# MEGA2560_Rev3e.net
KiCad netlist of a schematic drawn in EAGLE
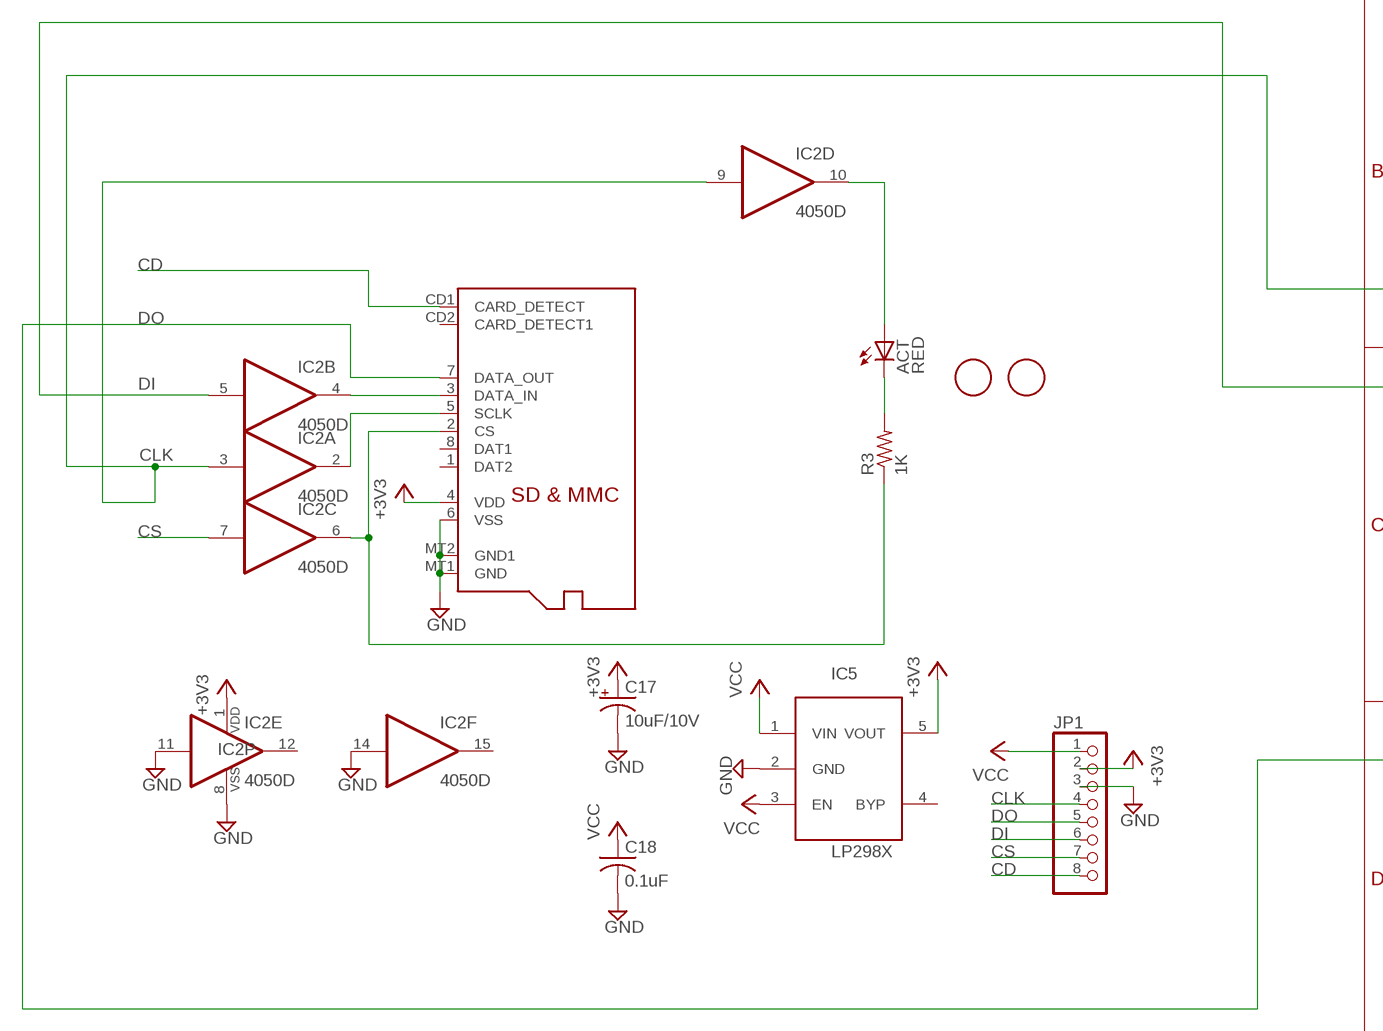
[diagram p0: schematic, sheet 1, part 1 of 2]
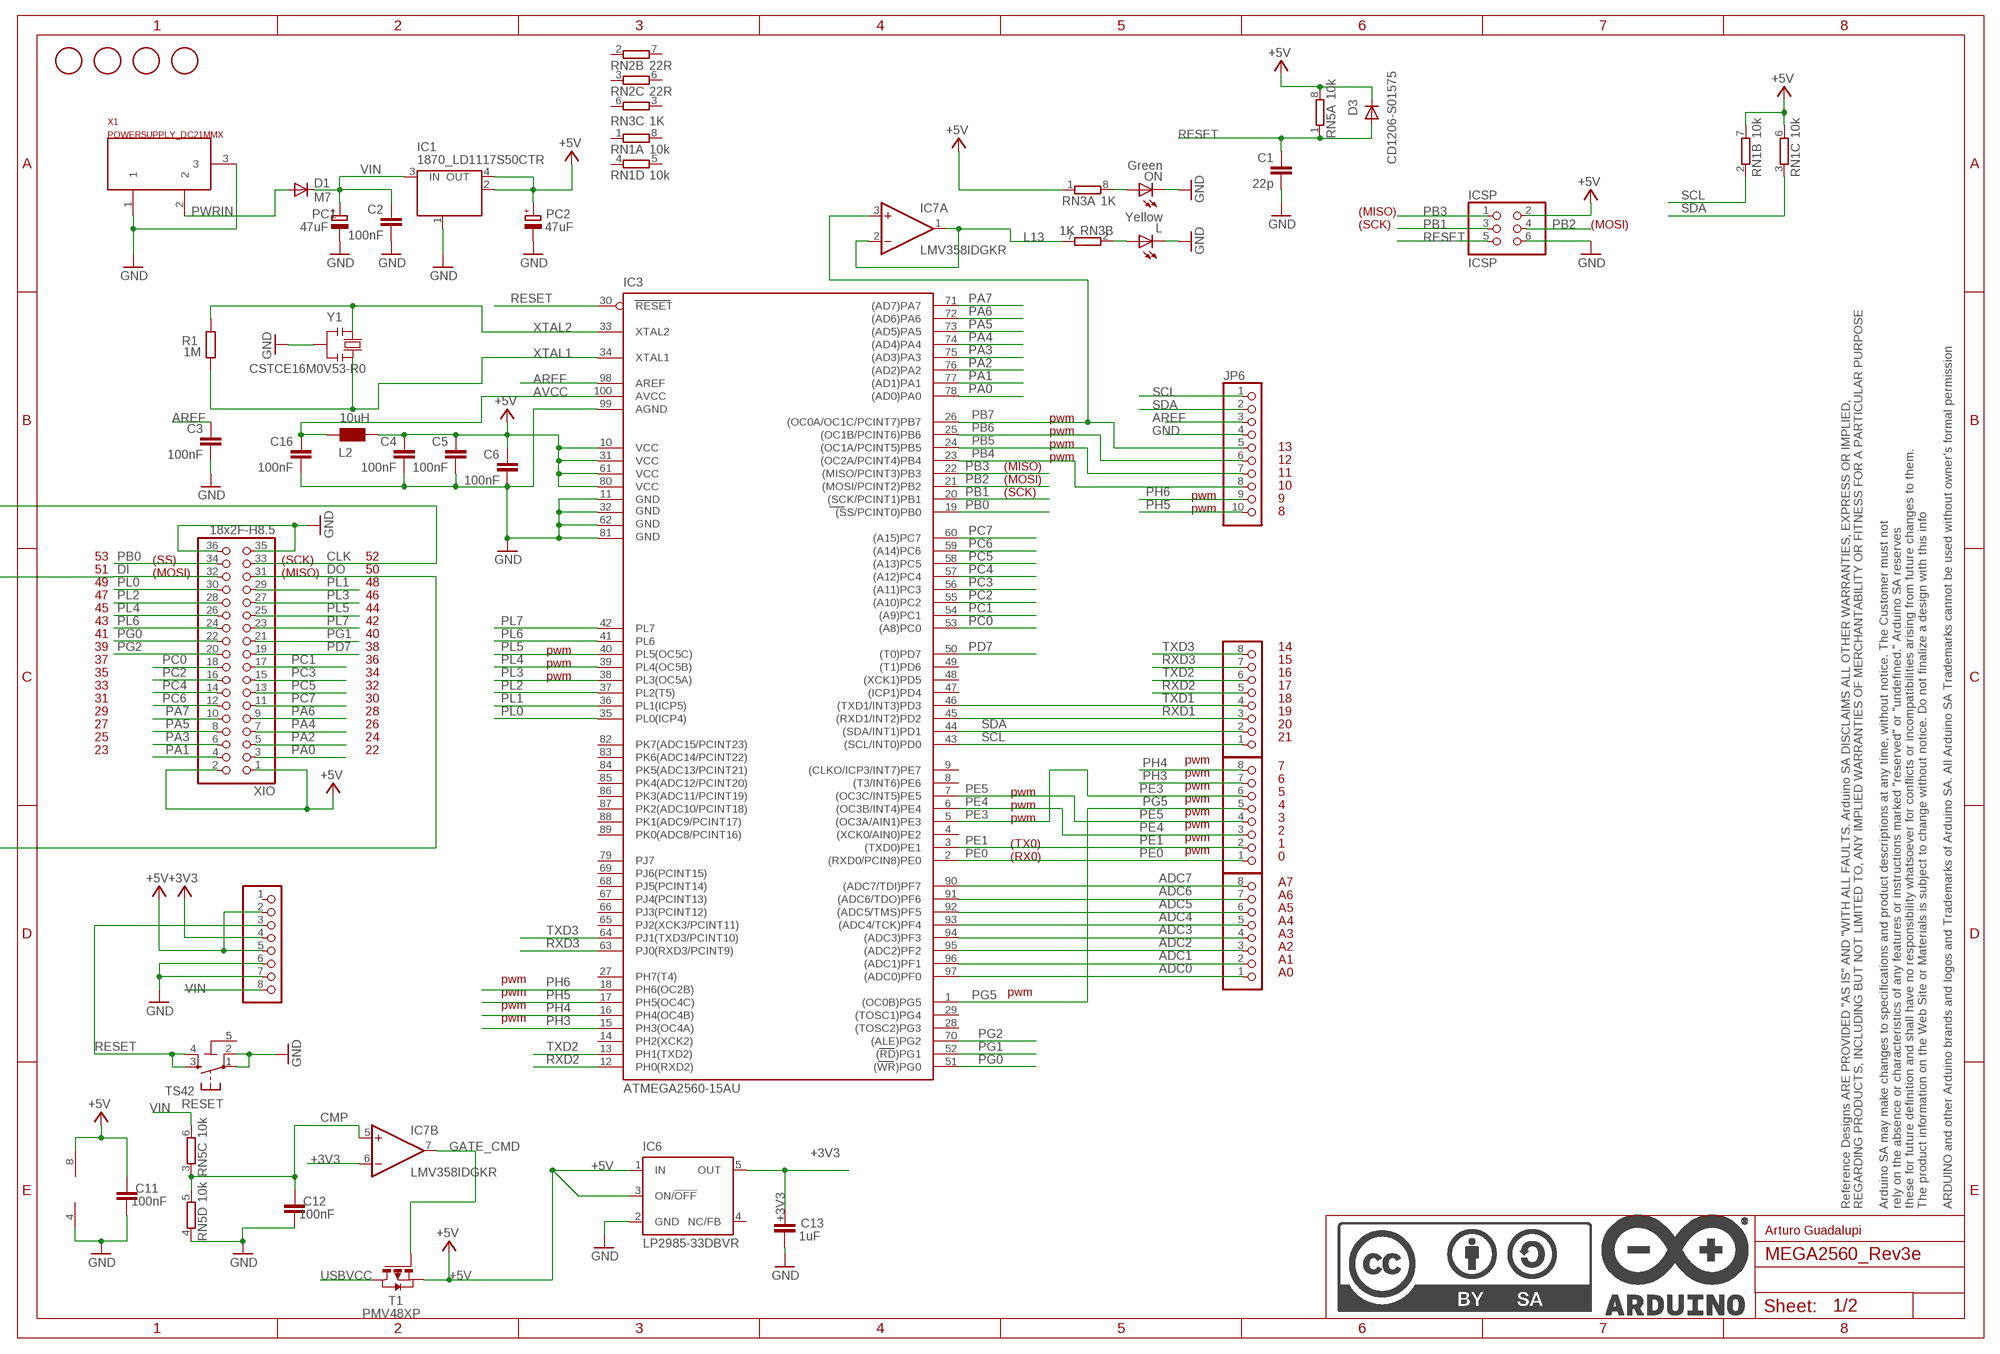
[diagram p1: schematic, sheet 1, part 2 of 2]
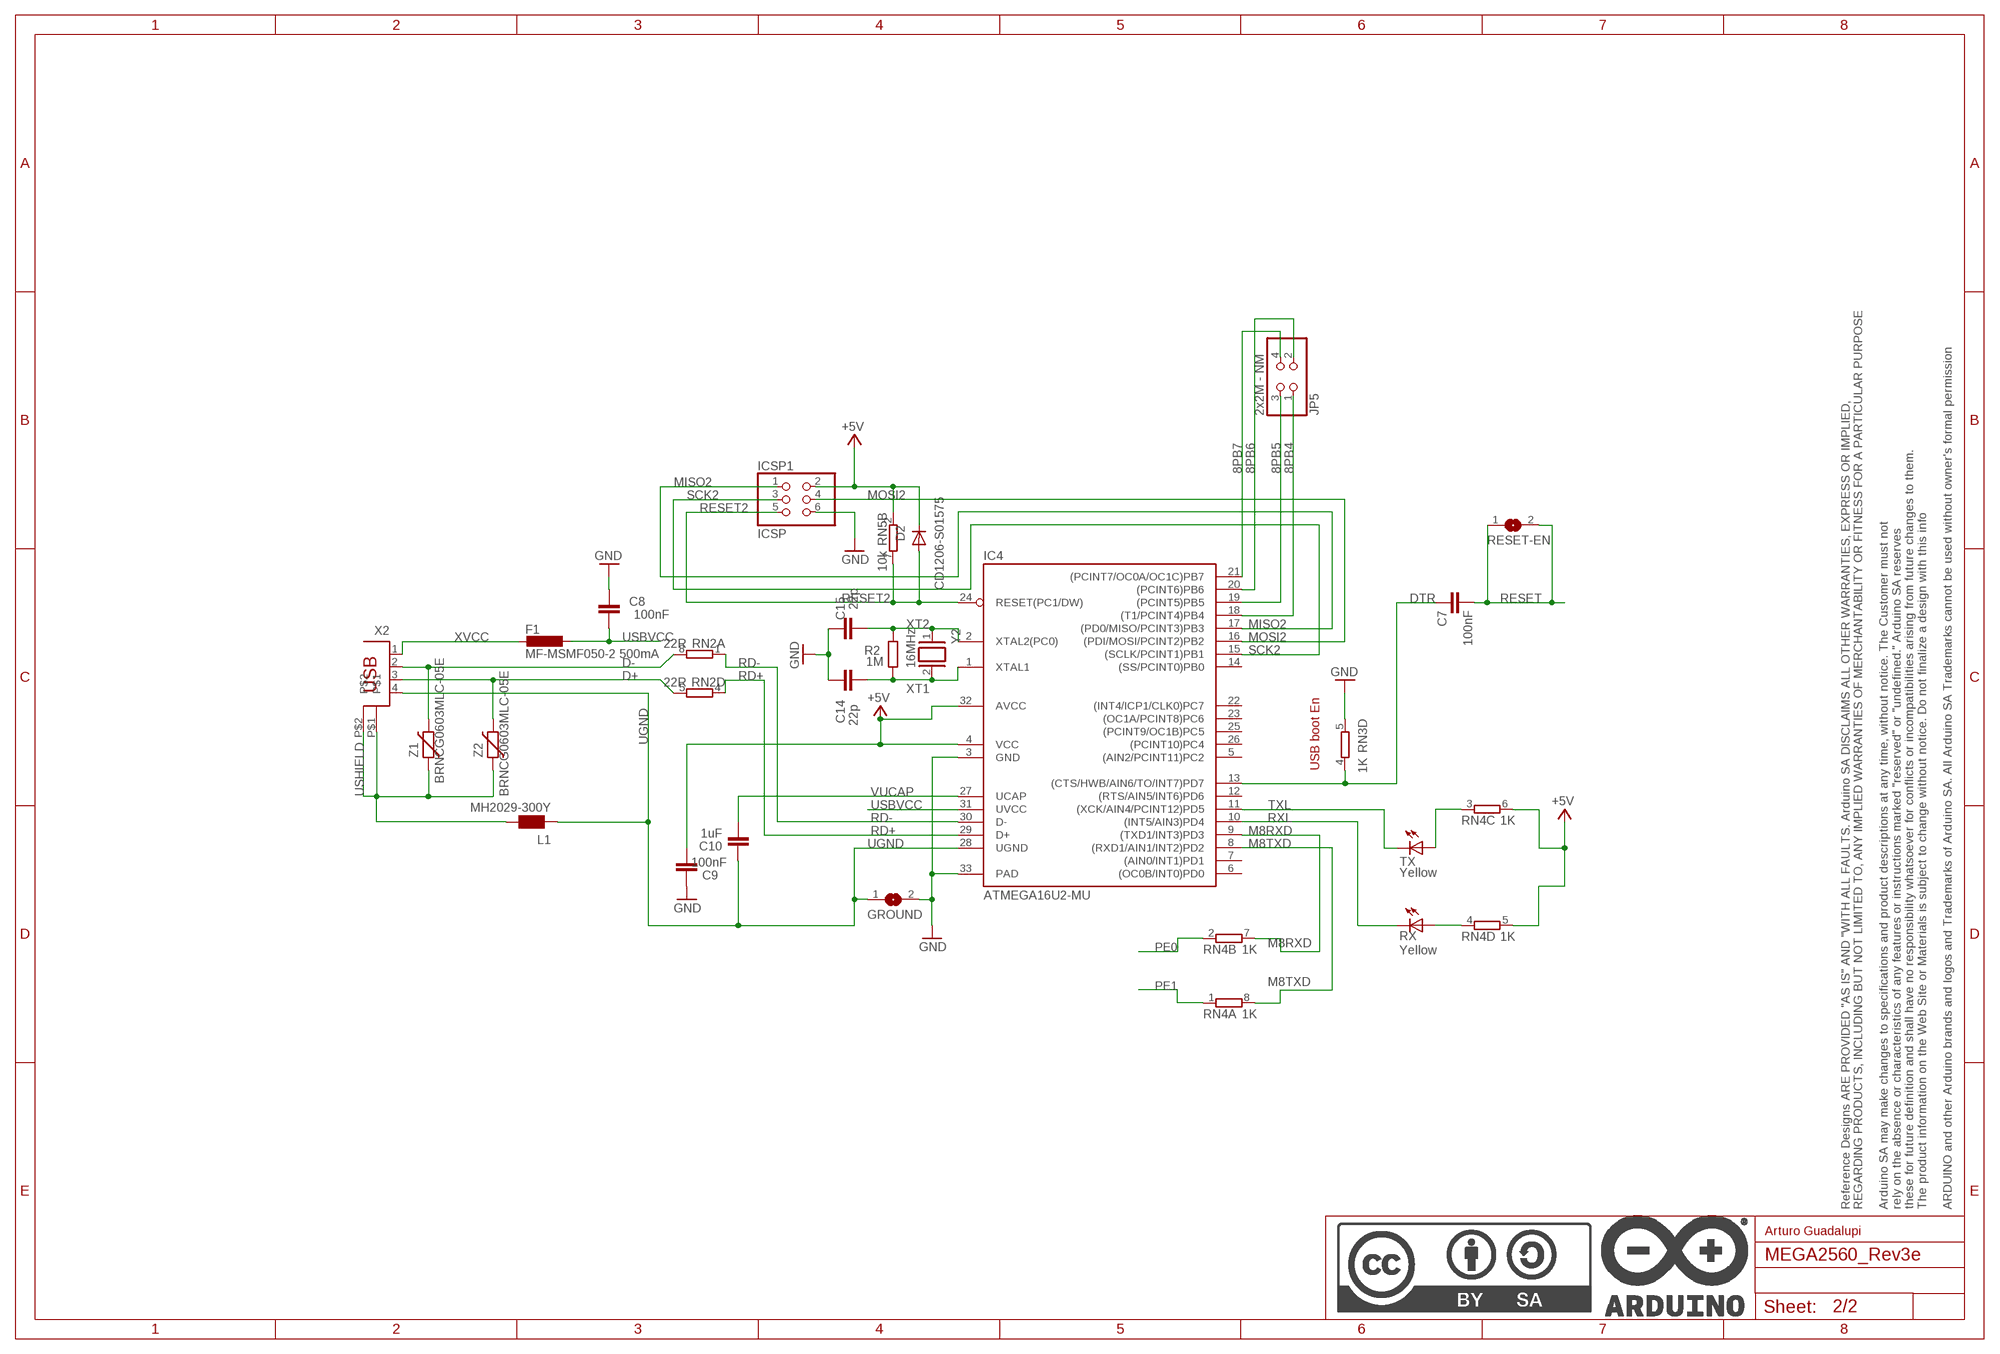
[diagram p2: schematic, sheet 2]

(export (version "E")
  (design (tool "Eeschema 10.0.6"))
  (components
    (comp (ref "C7")
      (value "100nF")
      (footprint "eagle-import:C0603-ROUND")
      (fields (field (name "PART_NUMBER") "cl10b104kbnc"))
      (libsource (lib "eagle-import") (part "0015_100NF_0603"))
    )
    (comp (ref "C8")
      (value "100nF")
      (footprint "eagle-import:C0603-ROUND")
      (fields (field (name "PART_NUMBER") "cl10b104kbnc"))
      (libsource (lib "eagle-import") (part "0015_100NF_0603"))
    )
    (comp (ref "C9")
      (value "100nF")
      (footprint "eagle-import:C0603-ROUND")
      (fields (field (name "PART_NUMBER") "cl10b104kbnc"))
      (libsource (lib "eagle-import") (part "0015_100NF_0603"))
    )
    (comp (ref "C10")
      (value "1uF")
      (footprint "eagle-import:C0603-ROUND")
      (fields (field (name "PART_NUMBER") "1uF_0603/GRM188R61E105KA12D"))
      (libsource (lib "eagle-import") (part "0006_1UF_0603/GRM188R61E105KA12D"))
    )
    (comp (ref "C14")
      (value "22p")
      (footprint "eagle-import:C0603-ROUND")
      (fields (field (name "PART_NUMBER") "22pF_0603"))
      (libsource (lib "eagle-import") (part "0014_22PF_0603"))
    )
    (comp (ref "C15")
      (value "22p")
      (footprint "eagle-import:C0603-ROUND")
      (fields (field (name "PART_NUMBER") "22pF_0603"))
      (libsource (lib "eagle-import") (part "0014_22PF_0603"))
    )
    (comp (ref "D2")
      (value "CD1206-S01575")
      (footprint "eagle-import:MINIMELF")
      (libsource (lib "eagle-import") (part "0012_CD1206-S01575"))
    )
    (comp (ref "F1")
      (value "MF-MSMF050-2 500mA")
      (footprint "eagle-import:L1812")
      (fields (field (name "PART_NUMBER") "MF-MSMF050-2"))
      (libsource (lib "eagle-import") (part "0002_MF-MSMF050-2"))
    )
    (comp (ref "GROUND")
      (value "SJ")
      (footprint "eagle-import:SJ")
      (libsource (lib "eagle-import") (part "SJ"))
    )
    (comp (ref "IC4")
      (value "ATMEGA16U2-MU")
      (footprint "eagle-import:MLF32")
      (fields (field (name "PART_NUMBER") "ATMEGA16U2-MUR"))
      (libsource (lib "eagle-import") (part "0007_ATMEGA16U2-MUR"))
    )
    (comp (ref "ICSP1")
      (value "ICSP")
      (footprint "eagle-import:2X03")
      (fields (field (name "PART_NUMBER") "PH254-203DF118A00V"))
      (libsource (lib "eagle-import") (part "0114_PH254-203DF118A00V"))
    )
    (comp (ref "JP5")
      (value "2x2M - NM")
      (footprint "eagle-import:2X02")
      (libsource (lib "eagle-import") (part "PINHD-2X2"))
    )
    (comp (ref "L1")
      (value "MH2029-300Y")
      (footprint "eagle-import:0805")
      (fields (field (name "PART_NUMBER") "BLM21PG300SN1D_/_MH2029-300Y"))
      (libsource (lib "eagle-import") (part "0001_BLM21PG300SN1D_/_MH2029-300Y"))
    )
    (comp (ref "R2")
      (value "1M")
      (footprint "eagle-import:R0603-ROUND")
      (fields (field (name "PART_NUMBER") "0603_1M"))
      (libsource (lib "eagle-import") (part "0004_0603_1M"))
    )
    (comp (ref "RESET-EN")
      (value "SJ")
      (footprint "eagle-import:SJ")
      (libsource (lib "eagle-import") (part "SJ"))
    )
    (comp (ref "RN2")
      (value "22R")
      (footprint "eagle-import:CAY16")
      (fields (field (name "PART_NUMBER") "064R_22R_/_CAY16-220J4LF"))
      (libsource (lib "eagle-import") (part "0003_064R_22R_/_CAY16-220J4LF"))
    )
    (comp (ref "RN3")
      (value "1K")
      (footprint "eagle-import:CAY16")
      (fields (field (name "PART_NUMBER") "064R_1K_/_CAY16-102J4LF"))
      (libsource (lib "eagle-import") (part "0005_064R_1K_/_CAY16-102J4LF"))
    )
    (comp (ref "RN4")
      (value "1K")
      (footprint "eagle-import:CAY16")
      (fields (field (name "PART_NUMBER") "064R_1K_/_CAY16-102J4LF"))
      (libsource (lib "eagle-import") (part "0005_064R_1K_/_CAY16-102J4LF"))
    )
    (comp (ref "RN5")
      (value "10k")
      (footprint "eagle-import:CAY16")
      (fields (field (name "PART_NUMBER") "064R_10K_/_CAY16-103J4LF"))
      (libsource (lib "eagle-import") (part "0016_064R_10K_/_CAY16-103J4LF"))
    )
    (comp (ref "RX")
      (value "Yellow")
      (footprint "eagle-import:CHIPLED_0805")
      (fields (field (name "PART_NUMBER") "KPT-2012YC"))
      (libsource (lib "eagle-import") (part "0044_KPT-2012YC"))
    )
    (comp (ref "TX")
      (value "Yellow")
      (footprint "eagle-import:CHIPLED_0805")
      (fields (field (name "PART_NUMBER") "KPT-2012YC"))
      (libsource (lib "eagle-import") (part "0044_KPT-2012YC"))
    )
    (comp (ref "U$2")
      (value "DNP")
      (footprint "eagle-import:FRAME")
      (libsource (lib "eagle-import") (part "A3-FRAME"))
    )
    (comp (ref "X2")
      (value "0056_USB-B-S-RA-WT-SPCC")
      (footprint "eagle-import:PN61729")
      (fields (field (name "PART_NUMBER") "USB-B-S-RA-WT-SPCC"))
      (libsource (lib "eagle-import") (part "0056_USB-B-S-RA-WT-SPCC"))
    )
    (comp (ref "Y2")
      (value "16MHz")
      (footprint "eagle-import:QS")
      (fields (field (name "PART_NUMBER") "P011052006 16M/FTX16M20S"))
      (libsource (lib "eagle-import") (part "0019_P011052006_16M"))
    )
    (comp (ref "Z1")
      (value "BRNCG0603MLC-05E")
      (footprint "eagle-import:CT_CN0603")
      (libsource (lib "eagle-import") (part "0010_BRNCG0603MLC-05E"))
    )
    (comp (ref "Z2")
      (value "BRNCG0603MLC-05E")
      (footprint "eagle-import:CT_CN0603")
      (libsource (lib "eagle-import") (part "0010_BRNCG0603MLC-05E"))
    )
    (comp (ref "ACT")
      (value "RED")
      (footprint "eagle-import:CHIP-LED0805")
      (libsource (lib "eagle-import") (part "LEDCHIP-LED0805"))
    )
    (comp (ref "ADCL")
      (value "FH254-108DF08500V")
      (footprint "eagle-import:1X08")
      (libsource (lib "eagle-import") (part "0058_FH254-108DF08500V"))
    )
    (comp (ref "C1")
      (value "22p")
      (footprint "eagle-import:C0603-ROUND")
      (fields (field (name "PART_NUMBER") "22pF_0603"))
      (libsource (lib "eagle-import") (part "0014_22PF_0603"))
    )
    (comp (ref "C2")
      (value "100nF")
      (footprint "eagle-import:C0603-ROUND")
      (fields (field (name "PART_NUMBER") "cl10b104kbnc"))
      (libsource (lib "eagle-import") (part "0015_100NF_0603"))
    )
    (comp (ref "C3")
      (value "100nF")
      (footprint "eagle-import:C0603-ROUND")
      (fields (field (name "PART_NUMBER") "cl10b104kbnc"))
      (libsource (lib "eagle-import") (part "0015_100NF_0603"))
    )
    (comp (ref "C4")
      (value "100nF")
      (footprint "eagle-import:C0603-ROUND")
      (fields (field (name "PART_NUMBER") "cl10b104kbnc"))
      (libsource (lib "eagle-import") (part "0015_100NF_0603"))
    )
    (comp (ref "C5")
      (value "100nF")
      (footprint "eagle-import:C0603-ROUND")
      (fields (field (name "PART_NUMBER") "cl10b104kbnc"))
      (libsource (lib "eagle-import") (part "0015_100NF_0603"))
    )
    (comp (ref "C6")
      (value "100nF")
      (footprint "eagle-import:C0603-ROUND")
      (fields (field (name "PART_NUMBER") "cl10b104kbnc"))
      (libsource (lib "eagle-import") (part "0015_100NF_0603"))
    )
    (comp (ref "C11")
      (value "100nF")
      (footprint "eagle-import:C0603-ROUND")
      (fields (field (name "PART_NUMBER") "cl10b104kbnc"))
      (libsource (lib "eagle-import") (part "0015_100NF_0603"))
    )
    (comp (ref "C12")
      (value "100nF")
      (footprint "eagle-import:C0603-ROUND")
      (fields (field (name "PART_NUMBER") "cl10b104kbnc"))
      (libsource (lib "eagle-import") (part "0015_100NF_0603"))
    )
    (comp (ref "C13")
      (value "1uF")
      (footprint "eagle-import:C0603-ROUND")
      (fields (field (name "PART_NUMBER") "1uF_0603/GRM188R61E105KA12D"))
      (libsource (lib "eagle-import") (part "0006_1UF_0603/GRM188R61E105KA12D"))
    )
    (comp (ref "C16")
      (value "100nF")
      (footprint "eagle-import:C0603-ROUND")
      (fields (field (name "PART_NUMBER") "cl10b104kbnc"))
      (libsource (lib "eagle-import") (part "0015_100NF_0603"))
    )
    (comp (ref "C17")
      (value "10uF/10V")
      (footprint "eagle-import:A_3216-18R")
      (libsource (lib "eagle-import") (part "CPOL-USA/3216-18R"))
    )
    (comp (ref "C18")
      (value "0.1uF")
      (footprint "eagle-import:C0805K")
      (libsource (lib "eagle-import") (part "C-USC0805K"))
    )
    (comp (ref "COMMUNICATION")
      (value "FH254-108DF08500V")
      (footprint "eagle-import:1X08")
      (libsource (lib "eagle-import") (part "0058_FH254-108DF08500V"))
    )
    (comp (ref "D1")
      (value "M7")
      (footprint "eagle-import:SMB")
      (libsource (lib "eagle-import") (part "0020_M7"))
    )
    (comp (ref "D3")
      (value "CD1206-S01575")
      (footprint "eagle-import:MINIMELF")
      (libsource (lib "eagle-import") (part "0012_CD1206-S01575"))
    )
    (comp (ref "FD1")
      (value "FIDUCIALMOUNT")
      (footprint "eagle-import:FIDUCIA-MOUNT")
      (libsource (lib "eagle-import") (part "FIDUCIALMOUNT"))
    )
    (comp (ref "FD2")
      (value "FIDUCIALMOUNT")
      (footprint "eagle-import:FIDUCIA-MOUNT")
      (libsource (lib "eagle-import") (part "FIDUCIALMOUNT"))
    )
    (comp (ref "FD3")
      (value "FIDUCIALMOUNT")
      (footprint "eagle-import:FIDUCIA-MOUNT")
      (libsource (lib "eagle-import") (part "FIDUCIALMOUNT"))
    )
    (comp (ref "FD4")
      (value "FIDUCIALMOUNT")
      (footprint "eagle-import:FIDUCIA-MOUNT")
      (libsource (lib "eagle-import") (part "FIDUCIALMOUNT"))
    )
    (comp (ref "IC1")
      (value "1870_LD1117S50CTR")
      (footprint "eagle-import:LINEAR_SOT223")
      (fields (field (name "PART_NUMBER") "LD1117S50CTR"))
      (libsource (lib "eagle-import") (part "1870_LD1117S50CTR"))
    )
    (comp (ref "IC2")
      (value "4050D")
      (footprint "eagle-import:SO16")
      (libsource (lib "eagle-import") (part "4050D"))
    )
    (comp (ref "IC3")
      (value "ATMEGA2560-15AU")
      (footprint "eagle-import:TQFP100")
      (fields (field (name "PART_NUMBER") "ATMEGA2560-16AU"))
      (libsource (lib "eagle-import") (part "0023_ATMEGA2560-16AU"))
    )
    (comp (ref "IC5")
      (value "LP298XS")
      (footprint "eagle-import:SOT23-5L")
      (libsource (lib "eagle-import") (part "LP298XS"))
    )
    (comp (ref "IC6")
      (value "LP2985-33DBVR")
      (footprint "eagle-import:SOT23-DBV")
      (fields (field (name "PART_NUMBER") "TEXLP2985-33DBVR"))
      (libsource (lib "eagle-import") (part "0008_TEXLP2985-33DBVR"))
    )
    (comp (ref "IC7")
      (value "LMV358IDGKR")
      (footprint "eagle-import:MSOP08")
      (libsource (lib "eagle-import") (part "0021_LMV358IDGKR"))
    )
    (comp (ref "ICSP")
      (value "ICSP")
      (footprint "eagle-import:2X03")
      (fields (field (name "PART_NUMBER") "PH254-203DF118A00V"))
      (libsource (lib "eagle-import") (part "0114_PH254-203DF118A00V"))
    )
    (comp (ref "JP1")
      (value "PINHD-1X8BIG")
      (footprint "eagle-import:1X08-BIG")
      (libsource (lib "eagle-import") (part "PINHD-1X8BIG"))
    )
    (comp (ref "JP6")
      (value "FH254-110DF08500V")
      (footprint "eagle-import:1X10")
      (fields (field (name "PART_NUMBER") "FH254-110DF08500T30"))
      (libsource (lib "eagle-import") (part "1216_FH254-110DF08500T30"))
    )
    (comp (ref "L")
      (value "Yellow")
      (footprint "eagle-import:CHIPLED_0805")
      (fields (field (name "PART_NUMBER") "KPT-2012YC"))
      (libsource (lib "eagle-import") (part "0044_KPT-2012YC"))
    )
    (comp (ref "L2")
      (value "10uH")
      (footprint "eagle-import:0805")
      (fields (field (name "PART_NUMBER") "CV201210-100K"))
      (libsource (lib "eagle-import") (part "0715_CV201210-100K"))
    )
    (comp (ref "ON")
      (value "Green")
      (footprint "eagle-import:CHIPLED_0805")
      (fields (field (name "PART_NUMBER") "KPT-2012SGC"))
      (libsource (lib "eagle-import") (part "0043_KPT-2012SGC"))
    )
    (comp (ref "PC1")
      (value "47uF")
      (footprint "eagle-import:PANASONIC_D")
      (libsource (lib "eagle-import") (part "0113_47UF"))
    )
    (comp (ref "PC2")
      (value "47uF")
      (footprint "eagle-import:PANASONIC_D")
      (libsource (lib "eagle-import") (part "0113_47UF"))
    )
    (comp (ref "POWER")
      (value "FH254-108DF08500V")
      (footprint "eagle-import:1X08")
      (fields (field (name "PART_NUMBER") "FH254-108DF08500T21"))
      (libsource (lib "eagle-import") (part "1217_FH254-108DF08500T21"))
    )
    (comp (ref "PWML")
      (value "FH254-108DF08500V")
      (footprint "eagle-import:1X08")
      (fields (field (name "PART_NUMBER") "FH254-108DF08500T20"))
      (libsource (lib "eagle-import") (part "1218_FH254-108DF08500T20"))
    )
    (comp (ref "R1")
      (value "1M")
      (footprint "eagle-import:R0603-ROUND")
      (fields (field (name "PART_NUMBER") "0603_1M"))
      (libsource (lib "eagle-import") (part "0004_0603_1M"))
    )
    (comp (ref "R3")
      (value "1K")
      (footprint "eagle-import:R0805")
      (libsource (lib "eagle-import") (part "R-US_R0805"))
    )
    (comp (ref "RESET")
      (value "TS42")
      (footprint "eagle-import:TS42")
      (fields (field (name "PART_NUMBER") "IT-1157AHNP-160G-G_GTR"))
      (libsource (lib "eagle-import") (part "0946_TS42031-160W-TR-7260"))
    )
    (comp (ref "RN1")
      (value "10k")
      (footprint "eagle-import:CAY16")
      (fields (field (name "PART_NUMBER") "064R_10K_/_CAY16-103J4LF"))
      (libsource (lib "eagle-import") (part "0016_064R_10K_/_CAY16-103J4LF"))
    )
    (comp (ref "T1")
      (value "PMV48XP")
      (footprint "eagle-import:SOT-23")
      (fields (field (name "CASE") "SOT23") (field (name "PART_NUMBER") "PMV48XP"))
      (libsource (lib "eagle-import") (part "0297_PMV48XP"))
    )
    (comp (ref "U$1")
      (value "DNP")
      (footprint "eagle-import:FRAME")
      (libsource (lib "eagle-import") (part "A3-FRAME"))
    )
    (comp (ref "U$3")
      (value "FIDUCIAL")
      (footprint "eagle-import:FIDUCIAL_1MM")
      (libsource (lib "eagle-import") (part "FIDUCIAL"))
    )
    (comp (ref "U$4")
      (value "FIDUCIAL")
      (footprint "eagle-import:FIDUCIAL_1MM")
      (libsource (lib "eagle-import") (part "FIDUCIAL"))
    )
    (comp (ref "X1")
      (value "POWERSUPPLY_DC21MMX")
      (footprint "eagle-import:POWERSUPPLY_DC-21MM")
      (libsource (lib "eagle-import") (part "POWERSUPPLY_DC21MMX"))
    )
    (comp (ref "X3")
      (value "MICROSD")
      (footprint "eagle-import:MICROSD")
      (libsource (lib "eagle-import") (part "MICROSD"))
    )
    (comp (ref "XIO")
      (value "18x2F-H8.5")
      (footprint "eagle-import:2X18")
      (fields (field (name "PART_NUMBER") "FH254-218DF08500V"))
      (libsource (lib "eagle-import") (part "0060_FH254-218DF08500V"))
    )
    (comp (ref "Y1")
      (value "CSTCE16M0V53-R0")
      (footprint "eagle-import:RESONATOR")
      (libsource (lib "eagle-import") (part "0011_CSTCE16M0V53-R0"))
    )
  )
  (nets
    (net (code "1") (name "+3V3") (class "Default")
      (node (ref "C13") (pin "2") (pinfunction "2_2") (pintype "passive"))
      (node (ref "C17") (pin "+") (pinfunction "+_+") (pintype "passive"))
      (node (ref "IC2") (pin "1") (pinfunction "VDD_1") (pintype "power_in"))
      (node (ref "IC5") (pin "5") (pinfunction "VOUT_5") (pintype "bidirectional"))
      (node (ref "IC6") (pin "5") (pinfunction "OUT_5") (pintype "passive"))
      (node (ref "IC7") (pin "6") (pinfunction "-IN_6") (pintype "input"))
      (node (ref "JP1") (pin "2") (pinfunction "2_2") (pintype "passive"))
      (node (ref "POWER") (pin "4") (pinfunction "4_4") (pintype "passive"))
      (node (ref "X3") (pin "4") (pinfunction "VDD_4") (pintype "power_in"))
    )
    (net (code "2") (name "+5V") (class "Default")
      (node (ref "C11") (pin "2") (pinfunction "2_2") (pintype "passive"))
      (node (ref "C4") (pin "1") (pinfunction "1_1") (pintype "passive"))
      (node (ref "C5") (pin "1") (pinfunction "1_1") (pintype "passive"))
      (node (ref "C6") (pin "1") (pinfunction "1_1") (pintype "passive"))
      (node (ref "C9") (pin "1") (pinfunction "1_1") (pintype "passive"))
      (node (ref "D2") (pin "C") (pinfunction "C_C") (pintype "passive"))
      (node (ref "D3") (pin "C") (pinfunction "C_C") (pintype "passive"))
      (node (ref "IC1") (pin "2") (pinfunction "OUT_2") (pintype "passive"))
      (node (ref "IC1") (pin "4") (pinfunction "OUT_4") (pintype "passive"))
      (node (ref "IC3") (pin "10") (pinfunction "VCC_10") (pintype "power_in"))
      (node (ref "IC3") (pin "31") (pinfunction "VCC1_31") (pintype "power_in"))
      (node (ref "IC3") (pin "61") (pinfunction "VCC2_61") (pintype "power_in"))
      (node (ref "IC3") (pin "80") (pinfunction "VCC3_80") (pintype "power_in"))
      (node (ref "IC4") (pin "32") (pinfunction "AVCC_32") (pintype "power_in"))
      (node (ref "IC4") (pin "4") (pinfunction "VCC_4") (pintype "power_in"))
      (node (ref "IC6") (pin "1") (pinfunction "IN_1") (pintype "input"))
      (node (ref "IC6") (pin "3") (pinfunction "ON/~{OFF}_3") (pintype "input"))
      (node (ref "IC7") (pin "8") (pinfunction "V+_8") (pintype "power_in"))
      (node (ref "ICSP") (pin "2") (pinfunction "2_2") (pintype "passive"))
      (node (ref "ICSP1") (pin "2") (pinfunction "2_2") (pintype "passive"))
      (node (ref "L2") (pin "2") (pinfunction "2_2") (pintype "passive"))
      (node (ref "PC2") (pin "+") (pinfunction "+_+") (pintype "passive"))
      (node (ref "POWER") (pin "2") (pinfunction "2_2") (pintype "passive"))
      (node (ref "POWER") (pin "5") (pinfunction "5_5") (pintype "passive"))
      (node (ref "RN1") (pin "6") (pinfunction "2_6") (pintype "passive"))
      (node (ref "RN1") (pin "7") (pinfunction "2_7") (pintype "passive"))
      (node (ref "RN3") (pin "1") (pinfunction "1_1") (pintype "passive"))
      (node (ref "RN4") (pin "5") (pinfunction "2_5") (pintype "passive"))
      (node (ref "RN4") (pin "6") (pinfunction "2_6") (pintype "passive"))
      (node (ref "RN5") (pin "2") (pinfunction "1_2") (pintype "passive"))
      (node (ref "RN5") (pin "8") (pinfunction "2_8") (pintype "passive"))
      (node (ref "T1") (pin "2") (pinfunction "S_2") (pintype "passive"))
      (node (ref "XIO") (pin "1") (pinfunction "1_1") (pintype "passive"))
      (node (ref "XIO") (pin "2") (pinfunction "2_2") (pintype "passive"))
    )
    (net (code "3") (name "5-GND") (class "Default")
      (node (ref "RESET") (pin "5") (pinfunction "5-GND_5") (pintype "power_in"))
    )
    (net (code "4") (name "8PB4") (class "Default")
      (node (ref "IC4") (pin "18") (pinfunction "(T1/PCINT4)PB4_18") (pintype "bidirectional"))
      (node (ref "JP5") (pin "1") (pinfunction "1_1") (pintype "passive"))
    )
    (net (code "5") (name "8PB5") (class "Default")
      (node (ref "IC4") (pin "19") (pinfunction "(PCINT5)PB5_19") (pintype "bidirectional"))
      (node (ref "JP5") (pin "3") (pinfunction "3_3") (pintype "passive"))
    )
    (net (code "6") (name "8PB6") (class "Default")
      (node (ref "IC4") (pin "20") (pinfunction "(PCINT6)PB6_20") (pintype "bidirectional"))
      (node (ref "JP5") (pin "2") (pinfunction "2_2") (pintype "passive"))
    )
    (net (code "7") (name "8PB7") (class "Default")
      (node (ref "IC4") (pin "21") (pinfunction "(PCINT7/OC0A/OC1C)PB7_21") (pintype "bidirectional"))
      (node (ref "JP5") (pin "4") (pinfunction "4_4") (pintype "passive"))
    )
    (net (code "8") (name "ADC0") (class "Default")
      (node (ref "ADCL") (pin "1") (pinfunction "1_1") (pintype "passive"))
      (node (ref "IC3") (pin "97") (pinfunction "(ADC0)PF0_97") (pintype "bidirectional"))
    )
    (net (code "9") (name "ADC1") (class "Default")
      (node (ref "ADCL") (pin "2") (pinfunction "2_2") (pintype "passive"))
      (node (ref "IC3") (pin "96") (pinfunction "(ADC1)PF1_96") (pintype "bidirectional"))
    )
    (net (code "10") (name "ADC2") (class "Default")
      (node (ref "ADCL") (pin "3") (pinfunction "3_3") (pintype "passive"))
      (node (ref "IC3") (pin "95") (pinfunction "(ADC2)PF2_95") (pintype "bidirectional"))
    )
    (net (code "11") (name "ADC3") (class "Default")
      (node (ref "ADCL") (pin "4") (pinfunction "4_4") (pintype "passive"))
      (node (ref "IC3") (pin "94") (pinfunction "(ADC3)PF3_94") (pintype "bidirectional"))
    )
    (net (code "12") (name "ADC4") (class "Default")
      (node (ref "ADCL") (pin "5") (pinfunction "5_5") (pintype "passive"))
      (node (ref "IC3") (pin "93") (pinfunction "(ADC4/TCK)PF4_93") (pintype "bidirectional"))
    )
    (net (code "13") (name "ADC5") (class "Default")
      (node (ref "ADCL") (pin "6") (pinfunction "6_6") (pintype "passive"))
      (node (ref "IC3") (pin "92") (pinfunction "(ADC5/TMS)PF5_92") (pintype "bidirectional"))
    )
    (net (code "14") (name "ADC6") (class "Default")
      (node (ref "ADCL") (pin "7") (pinfunction "7_7") (pintype "passive"))
      (node (ref "IC3") (pin "91") (pinfunction "(ADC6/TDO)PF6_91") (pintype "bidirectional"))
    )
    (net (code "15") (name "ADC7") (class "Default")
      (node (ref "ADCL") (pin "8") (pinfunction "8_8") (pintype "passive"))
      (node (ref "IC3") (pin "90") (pinfunction "(ADC7/TDI)PF7_90") (pintype "bidirectional"))
    )
    (net (code "16") (name "AREF") (class "Default")
      (node (ref "C3") (pin "1") (pinfunction "1_1") (pintype "passive"))
      (node (ref "IC3") (pin "98") (pinfunction "AREF_98") (pintype "bidirectional"))
      (node (ref "JP6") (pin "3") (pinfunction "3_3") (pintype "passive"))
    )
    (net (code "17") (name "AVCC") (class "Default")
      (node (ref "C16") (pin "1") (pinfunction "1_1") (pintype "passive"))
      (node (ref "IC3") (pin "100") (pinfunction "AVCC_100") (pintype "power_in"))
      (node (ref "L2") (pin "1") (pinfunction "1_1") (pintype "passive"))
    )
    (net (code "18") (name "CD") (class "Default")
      (node (ref "JP1") (pin "8") (pinfunction "8_8") (pintype "passive"))
      (node (ref "X3") (pin "CD1") (pinfunction "CARD_DETECT_CD1") (pintype "passive"))
    )
    (net (code "19") (name "CLK") (class "Default")
      (node (ref "IC2") (pin "3") (pinfunction "I_3") (pintype "input"))
      (node (ref "IC2") (pin "9") (pinfunction "I_9") (pintype "input"))
      (node (ref "JP1") (pin "4") (pinfunction "4_4") (pintype "passive"))
      (node (ref "XIO") (pin "33") (pinfunction "33_33") (pintype "passive"))
    )
    (net (code "20") (name "CMP") (class "Default")
      (node (ref "C12") (pin "2") (pinfunction "2_2") (pintype "passive"))
      (node (ref "IC7") (pin "5") (pinfunction "+IN_5") (pintype "input"))
      (node (ref "RN5") (pin "3") (pinfunction "1_3") (pintype "passive"))
      (node (ref "RN5") (pin "5") (pinfunction "2_5") (pintype "passive"))
    )
    (net (code "21") (name "CS") (class "Default")
      (node (ref "IC2") (pin "7") (pinfunction "I_7") (pintype "input"))
      (node (ref "JP1") (pin "7") (pinfunction "7_7") (pintype "passive"))
    )
    (net (code "22") (name "D+") (class "Default")
      (node (ref "RN2") (pin "5") (pinfunction "2_5") (pintype "passive"))
      (node (ref "X2") (pin "3") (pinfunction "3_3") (pintype "bidirectional"))
      (node (ref "Z2") (pin "2") (pinfunction "2_2") (pintype "passive"))
    )
    (net (code "23") (name "D-") (class "Default")
      (node (ref "RN2") (pin "8") (pinfunction "2_8") (pintype "passive"))
      (node (ref "X2") (pin "2") (pinfunction "2_2") (pintype "bidirectional"))
      (node (ref "Z1") (pin "2") (pinfunction "2_2") (pintype "passive"))
    )
    (net (code "24") (name "DI") (class "Default")
      (node (ref "IC2") (pin "5") (pinfunction "I_5") (pintype "input"))
      (node (ref "JP1") (pin "6") (pinfunction "6_6") (pintype "passive"))
      (node (ref "XIO") (pin "32") (pinfunction "32_32") (pintype "passive"))
    )
    (net (code "25") (name "DO") (class "Default")
      (node (ref "JP1") (pin "5") (pinfunction "5_5") (pintype "passive"))
      (node (ref "X3") (pin "7") (pinfunction "DATA_OUT_7") (pintype "output"))
      (node (ref "XIO") (pin "31") (pinfunction "31_31") (pintype "passive"))
    )
    (net (code "26") (name "DTR") (class "Default")
      (node (ref "C7") (pin "1") (pinfunction "1_1") (pintype "passive"))
      (node (ref "IC4") (pin "13") (pinfunction "(CTS/HWB/AIN6/TO/INT7)PD7_13") (pintype "bidirectional"))
      (node (ref "RN3") (pin "4") (pinfunction "1_4") (pintype "passive"))
    )
    (net (code "27") (name "GATE_CMD") (class "Default")
      (node (ref "IC7") (pin "7") (pinfunction "OUT_7") (pintype "output"))
      (node (ref "T1") (pin "3") (pinfunction "G_3") (pintype "passive"))
    )
    (net (code "28") (name "GND") (class "Default")
      (node (ref "C1") (pin "2") (pinfunction "2_2") (pintype "passive"))
      (node (ref "C11") (pin "1") (pinfunction "1_1") (pintype "passive"))
      (node (ref "C12") (pin "1") (pinfunction "1_1") (pintype "passive"))
      (node (ref "C13") (pin "1") (pinfunction "1_1") (pintype "passive"))
      (node (ref "C14") (pin "2") (pinfunction "2_2") (pintype "passive"))
      (node (ref "C15") (pin "2") (pinfunction "2_2") (pintype "passive"))
      (node (ref "C16") (pin "2") (pinfunction "2_2") (pintype "passive"))
      (node (ref "C17") (pin "-") (pinfunction "-_-") (pintype "passive"))
      (node (ref "C18") (pin "2") (pinfunction "2_2") (pintype "passive"))
      (node (ref "C2") (pin "2") (pinfunction "2_2") (pintype "passive"))
      (node (ref "C3") (pin "2") (pinfunction "2_2") (pintype "passive"))
      (node (ref "C4") (pin "2") (pinfunction "2_2") (pintype "passive"))
      (node (ref "C5") (pin "2") (pinfunction "2_2") (pintype "passive"))
      (node (ref "C6") (pin "2") (pinfunction "2_2") (pintype "passive"))
      (node (ref "C8") (pin "2") (pinfunction "2_2") (pintype "passive"))
      (node (ref "C9") (pin "2") (pinfunction "2_2") (pintype "passive"))
      (node (ref "GROUND") (pin "2") (pinfunction "2_2") (pintype "passive"))
      (node (ref "IC1") (pin "1") (pinfunction "GND/ADJ_1") (pintype "input"))
      (node (ref "IC2") (pin "11") (pinfunction "I_11") (pintype "input"))
      (node (ref "IC2") (pin "14") (pinfunction "I_14") (pintype "input"))
      (node (ref "IC2") (pin "8") (pinfunction "VSS_8") (pintype "power_in"))
      (node (ref "IC3") (pin "11") (pinfunction "GND_11") (pintype "power_in"))
      (node (ref "IC3") (pin "32") (pinfunction "GND1_32") (pintype "power_in"))
      (node (ref "IC3") (pin "62") (pinfunction "GND2_62") (pintype "power_in"))
      (node (ref "IC3") (pin "81") (pinfunction "GND3_81") (pintype "power_in"))
      (node (ref "IC3") (pin "99") (pinfunction "AGND_99") (pintype "power_in"))
      (node (ref "IC4") (pin "3") (pinfunction "GND_3") (pintype "power_in"))
      (node (ref "IC4") (pin "33") (pinfunction "PAD_33") (pintype "power_in"))
      (node (ref "IC5") (pin "2") (pinfunction "GND_2") (pintype "bidirectional"))
      (node (ref "IC6") (pin "2") (pinfunction "GND_2") (pintype "power_in"))
      (node (ref "IC7") (pin "4") (pinfunction "V-_4") (pintype "power_in"))
      (node (ref "ICSP") (pin "6") (pinfunction "6_6") (pintype "passive"))
      (node (ref "ICSP1") (pin "6") (pinfunction "6_6") (pintype "passive"))
      (node (ref "JP1") (pin "3") (pinfunction "3_3") (pintype "passive"))
      (node (ref "JP6") (pin "4") (pinfunction "4_4") (pintype "passive"))
      (node (ref "L") (pin "C") (pinfunction "C_C") (pintype "passive"))
      (node (ref "ON") (pin "C") (pinfunction "C_C") (pintype "passive"))
      (node (ref "PC1") (pin "-") (pinfunction "-_-") (pintype "passive"))
      (node (ref "PC2") (pin "-") (pinfunction "-_-") (pintype "passive"))
      (node (ref "POWER") (pin "6") (pinfunction "6_6") (pintype "passive"))
      (node (ref "POWER") (pin "7") (pinfunction "7_7") (pintype "passive"))
      (node (ref "RESET") (pin "1") (pinfunction "1_1") (pintype "passive"))
      (node (ref "RESET") (pin "2") (pinfunction "2_2") (pintype "passive"))
      (node (ref "RN3") (pin "5") (pinfunction "2_5") (pintype "passive"))
      (node (ref "RN5") (pin "4") (pinfunction "1_4") (pintype "passive"))
      (node (ref "X1") (pin "1") (pinfunction "1_1") (pintype "power_in"))
      (node (ref "X1") (pin "3") (pinfunction "3_3") (pintype "power_in"))
      (node (ref "X3") (pin "6") (pinfunction "VSS_6") (pintype "power_in"))
      (node (ref "X3") (pin "MT1") (pinfunction "GND_MT1") (pintype "power_in"))
      (node (ref "X3") (pin "MT2") (pinfunction "GND1_MT2") (pintype "power_in"))
      (node (ref "XIO") (pin "35") (pinfunction "35_35") (pintype "passive"))
      (node (ref "XIO") (pin "36") (pinfunction "36_36") (pintype "passive"))
      (node (ref "Y1") (pin "2") (pinfunction "2_2") (pintype "passive"))
    )
    (net (code "29") (name "L13") (class "Default")
      (node (ref "IC7") (pin "1") (pinfunction "OUT_1") (pintype "output"))
      (node (ref "IC7") (pin "2") (pinfunction "-IN_2") (pintype "input"))
      (node (ref "RN3") (pin "7") (pinfunction "2_7") (pintype "passive"))
    )
    (net (code "30") (name "M8RXD") (class "Default")
      (node (ref "IC4") (pin "9") (pinfunction "(TXD1/INT3)PD3_9") (pintype "bidirectional"))
      (node (ref "RN4") (pin "7") (pinfunction "2_7") (pintype "passive"))
    )
    (net (code "31") (name "M8TXD") (class "Default")
      (node (ref "IC4") (pin "8") (pinfunction "(RXD1/AIN1/INT2)PD2_8") (pintype "bidirectional"))
      (node (ref "RN4") (pin "8") (pinfunction "2_8") (pintype "passive"))
    )
    (net (code "32") (name "MISO2") (class "Default")
      (node (ref "IC4") (pin "17") (pinfunction "(PD0/MISO/PCINT3)PB3_17") (pintype "bidirectional"))
      (node (ref "ICSP1") (pin "1") (pinfunction "1_1") (pintype "passive"))
    )
    (net (code "33") (name "MOSI2") (class "Default")
      (node (ref "IC4") (pin "16") (pinfunction "(PDI/MOSI/PCINT2)PB2_16") (pintype "bidirectional"))
      (node (ref "ICSP1") (pin "4") (pinfunction "4_4") (pintype "passive"))
    )
    (net (code "34") (name "Net-(ACT-PadC)") (class "Default")
      (node (ref "ACT") (pin "C") (pinfunction "C_C") (pintype "passive"))
      (node (ref "R3") (pin "2") (pinfunction "2_2") (pintype "passive"))
    )
    (net (code "35") (name "Net-(IC2A-O)") (class "Default")
      (node (ref "IC2") (pin "2") (pinfunction "O_2") (pintype "output"))
      (node (ref "X3") (pin "5") (pinfunction "SCLK_5") (pintype "input"))
    )
    (net (code "36") (name "Net-(IC2B-O)") (class "Default")
      (node (ref "IC2") (pin "4") (pinfunction "O_4") (pintype "output"))
      (node (ref "X3") (pin "3") (pinfunction "DATA_IN_3") (pintype "input"))
    )
    (net (code "37") (name "Net-(IC2C-O)") (class "Default")
      (node (ref "IC2") (pin "6") (pinfunction "O_6") (pintype "output"))
      (node (ref "R3") (pin "1") (pinfunction "1_1") (pintype "passive"))
      (node (ref "X3") (pin "2") (pinfunction "CS_2") (pintype "input"))
    )
    (net (code "38") (name "Net-(IC2D-O)") (class "Default")
      (node (ref "ACT") (pin "A") (pinfunction "A_A") (pintype "passive"))
      (node (ref "IC2") (pin "10") (pinfunction "O_10") (pintype "output"))
    )
    (net (code "39") (name "Net-(RN3A-2)") (class "Default")
      (node (ref "ON") (pin "A") (pinfunction "A_A") (pintype "passive"))
      (node (ref "RN3") (pin "8") (pinfunction "2_8") (pintype "passive"))
    )
    (net (code "40") (name "Net-(RN3B-1)") (class "Default")
      (node (ref "L") (pin "A") (pinfunction "A_A") (pintype "passive"))
      (node (ref "RN3") (pin "2") (pinfunction "1_2") (pintype "passive"))
    )
    (net (code "41") (name "Net-(RN4C-1)") (class "Default")
      (node (ref "RN4") (pin "3") (pinfunction "1_3") (pintype "passive"))
      (node (ref "TX") (pin "A") (pinfunction "A_A") (pintype "passive"))
    )
    (net (code "42") (name "Net-(RN4D-1)") (class "Default")
      (node (ref "RN4") (pin "4") (pinfunction "1_4") (pintype "passive"))
      (node (ref "RX") (pin "A") (pinfunction "A_A") (pintype "passive"))
    )
    (net (code "43") (name "PA0") (class "Default")
      (node (ref "IC3") (pin "78") (pinfunction "(AD0)PA0_78") (pintype "bidirectional"))
      (node (ref "XIO") (pin "3") (pinfunction "3_3") (pintype "passive"))
    )
    (net (code "44") (name "PA1") (class "Default")
      (node (ref "IC3") (pin "77") (pinfunction "(AD1)PA1_77") (pintype "bidirectional"))
      (node (ref "XIO") (pin "4") (pinfunction "4_4") (pintype "passive"))
    )
    (net (code "45") (name "PA2") (class "Default")
      (node (ref "IC3") (pin "76") (pinfunction "(AD2)PA2_76") (pintype "bidirectional"))
      (node (ref "XIO") (pin "5") (pinfunction "5_5") (pintype "passive"))
    )
    (net (code "46") (name "PA3") (class "Default")
      (node (ref "IC3") (pin "75") (pinfunction "(AD3)PA3_75") (pintype "bidirectional"))
      (node (ref "XIO") (pin "6") (pinfunction "6_6") (pintype "passive"))
    )
    (net (code "47") (name "PA4") (class "Default")
      (node (ref "IC3") (pin "74") (pinfunction "(AD4)PA4_74") (pintype "bidirectional"))
      (node (ref "XIO") (pin "7") (pinfunction "7_7") (pintype "passive"))
    )
    (net (code "48") (name "PA5") (class "Default")
      (node (ref "IC3") (pin "73") (pinfunction "(AD5)PA5_73") (pintype "bidirectional"))
      (node (ref "XIO") (pin "8") (pinfunction "8_8") (pintype "passive"))
    )
    (net (code "49") (name "PA6") (class "Default")
      (node (ref "IC3") (pin "72") (pinfunction "(AD6)PA6_72") (pintype "bidirectional"))
      (node (ref "XIO") (pin "9") (pinfunction "9_9") (pintype "passive"))
    )
    (net (code "50") (name "PA7") (class "Default")
      (node (ref "IC3") (pin "71") (pinfunction "(AD7)PA7_71") (pintype "bidirectional"))
      (node (ref "XIO") (pin "10") (pinfunction "10_10") (pintype "passive"))
    )
    (net (code "51") (name "PB0") (class "Default")
      (node (ref "IC3") (pin "19") (pinfunction "(SS/PCINT0)PB0_19") (pintype "bidirectional"))
      (node (ref "XIO") (pin "34") (pinfunction "34_34") (pintype "passive"))
    )
    (net (code "52") (name "PB1") (class "Default")
      (node (ref "IC3") (pin "20") (pinfunction "(SCK/PCINT1)PB1_20") (pintype "bidirectional"))
      (node (ref "ICSP") (pin "3") (pinfunction "3_3") (pintype "passive"))
    )
    (net (code "53") (name "PB2") (class "Default")
      (node (ref "IC3") (pin "21") (pinfunction "(MOSI/PCINT2)PB2_21") (pintype "bidirectional"))
      (node (ref "ICSP") (pin "4") (pinfunction "4_4") (pintype "passive"))
    )
    (net (code "54") (name "PB3") (class "Default")
      (node (ref "IC3") (pin "22") (pinfunction "(MISO/PCINT3)PB3_22") (pintype "bidirectional"))
      (node (ref "ICSP") (pin "1") (pinfunction "1_1") (pintype "passive"))
    )
    (net (code "55") (name "PB4") (class "Default")
      (node (ref "IC3") (pin "23") (pinfunction "(OC2A/PCINT4)PB4_23") (pintype "bidirectional"))
      (node (ref "JP6") (pin "8") (pinfunction "8_8") (pintype "passive"))
    )
    (net (code "56") (name "PB5") (class "Default")
      (node (ref "IC3") (pin "24") (pinfunction "(OC1A/PCINT5)PB5_24") (pintype "bidirectional"))
      (node (ref "JP6") (pin "7") (pinfunction "7_7") (pintype "passive"))
    )
    (net (code "57") (name "PB6") (class "Default")
      (node (ref "IC3") (pin "25") (pinfunction "(OC1B/PCINT6)PB6_25") (pintype "bidirectional"))
      (node (ref "JP6") (pin "6") (pinfunction "6_6") (pintype "passive"))
    )
    (net (code "58") (name "PB7") (class "Default")
      (node (ref "IC3") (pin "26") (pinfunction "(OC0A/OC1C/PCINT7)PB7_26") (pintype "bidirectional"))
      (node (ref "IC7") (pin "3") (pinfunction "+IN_3") (pintype "input"))
      (node (ref "JP6") (pin "5") (pinfunction "5_5") (pintype "passive"))
    )
    (net (code "59") (name "PC0") (class "Default")
      (node (ref "IC3") (pin "53") (pinfunction "(A8)PC0_53") (pintype "bidirectional"))
      (node (ref "XIO") (pin "18") (pinfunction "18_18") (pintype "passive"))
    )
    (net (code "60") (name "PC1") (class "Default")
      (node (ref "IC3") (pin "54") (pinfunction "(A9)PC1_54") (pintype "bidirectional"))
      (node (ref "XIO") (pin "17") (pinfunction "17_17") (pintype "passive"))
    )
    (net (code "61") (name "PC2") (class "Default")
      (node (ref "IC3") (pin "55") (pinfunction "(A10)PC2_55") (pintype "bidirectional"))
      (node (ref "XIO") (pin "16") (pinfunction "16_16") (pintype "passive"))
    )
    (net (code "62") (name "PC3") (class "Default")
      (node (ref "IC3") (pin "56") (pinfunction "(A11)PC3_56") (pintype "bidirectional"))
      (node (ref "XIO") (pin "15") (pinfunction "15_15") (pintype "passive"))
    )
    (net (code "63") (name "PC4") (class "Default")
      (node (ref "IC3") (pin "57") (pinfunction "(A12)PC4_57") (pintype "bidirectional"))
      (node (ref "XIO") (pin "14") (pinfunction "14_14") (pintype "passive"))
    )
    (net (code "64") (name "PC5") (class "Default")
      (node (ref "IC3") (pin "58") (pinfunction "(A13)PC5_58") (pintype "bidirectional"))
      (node (ref "XIO") (pin "13") (pinfunction "13_13") (pintype "passive"))
    )
    (net (code "65") (name "PC6") (class "Default")
      (node (ref "IC3") (pin "59") (pinfunction "(A14)PC6_59") (pintype "bidirectional"))
      (node (ref "XIO") (pin "12") (pinfunction "12_12") (pintype "passive"))
    )
    (net (code "66") (name "PC7") (class "Default")
      (node (ref "IC3") (pin "60") (pinfunction "(A15)PC7_60") (pintype "bidirectional"))
      (node (ref "XIO") (pin "11") (pinfunction "11_11") (pintype "passive"))
    )
    (net (code "67") (name "PD7") (class "Default")
      (node (ref "IC3") (pin "50") (pinfunction "(T0)PD7_50") (pintype "bidirectional"))
      (node (ref "XIO") (pin "19") (pinfunction "19_19") (pintype "passive"))
    )
    (net (code "68") (name "PE0") (class "Default")
      (node (ref "IC3") (pin "2") (pinfunction "(RXD0/PCIN8)PE0_2") (pintype "bidirectional"))
      (node (ref "PWML") (pin "1") (pinfunction "1_1") (pintype "passive"))
      (node (ref "RN4") (pin "2") (pinfunction "1_2") (pintype "passive"))
    )
    (net (code "69") (name "PE1") (class "Default")
      (node (ref "IC3") (pin "3") (pinfunction "(TXD0)PE1_3") (pintype "bidirectional"))
      (node (ref "PWML") (pin "2") (pinfunction "2_2") (pintype "passive"))
      (node (ref "RN4") (pin "1") (pinfunction "1_1") (pintype "passive"))
    )
    (net (code "70") (name "PE3") (class "Default")
      (node (ref "IC3") (pin "5") (pinfunction "(OC3A/AIN1)PE3_5") (pintype "bidirectional"))
      (node (ref "PWML") (pin "6") (pinfunction "6_6") (pintype "passive"))
    )
    (net (code "71") (name "PE4") (class "Default")
      (node (ref "IC3") (pin "6") (pinfunction "(OC3B/INT4)PE4_6") (pintype "bidirectional"))
      (node (ref "PWML") (pin "3") (pinfunction "3_3") (pintype "passive"))
    )
    (net (code "72") (name "PE5") (class "Default")
      (node (ref "IC3") (pin "7") (pinfunction "(OC3C/INT5)PE5_7") (pintype "bidirectional"))
      (node (ref "PWML") (pin "4") (pinfunction "4_4") (pintype "passive"))
    )
    (net (code "73") (name "PG0") (class "Default")
      (node (ref "IC3") (pin "51") (pinfunction "(WR)PG0_51") (pintype "bidirectional"))
      (node (ref "XIO") (pin "22") (pinfunction "22_22") (pintype "passive"))
    )
    (net (code "74") (name "PG1") (class "Default")
      (node (ref "IC3") (pin "52") (pinfunction "(RD)PG1_52") (pintype "bidirectional"))
      (node (ref "XIO") (pin "21") (pinfunction "21_21") (pintype "passive"))
    )
    (net (code "75") (name "PG2") (class "Default")
      (node (ref "IC3") (pin "70") (pinfunction "(ALE)PG2_70") (pintype "bidirectional"))
      (node (ref "XIO") (pin "20") (pinfunction "20_20") (pintype "passive"))
    )
    (net (code "76") (name "PG5") (class "Default")
      (node (ref "IC3") (pin "1") (pinfunction "(OC0B)PG5_1") (pintype "bidirectional"))
      (node (ref "PWML") (pin "5") (pinfunction "5_5") (pintype "passive"))
    )
    (net (code "77") (name "PH3") (class "Default")
      (node (ref "IC3") (pin "15") (pinfunction "PH3(OC4A)_15") (pintype "bidirectional"))
      (node (ref "PWML") (pin "7") (pinfunction "7_7") (pintype "passive"))
    )
    (net (code "78") (name "PH4") (class "Default")
      (node (ref "IC3") (pin "16") (pinfunction "PH4(OC4B)_16") (pintype "bidirectional"))
      (node (ref "PWML") (pin "8") (pinfunction "8_8") (pintype "passive"))
    )
    (net (code "79") (name "PH5") (class "Default")
      (node (ref "IC3") (pin "17") (pinfunction "PH5(OC4C)_17") (pintype "bidirectional"))
      (node (ref "JP6") (pin "10") (pinfunction "10_10") (pintype "passive"))
    )
    (net (code "80") (name "PH6") (class "Default")
      (node (ref "IC3") (pin "18") (pinfunction "PH6(OC2B)_18") (pintype "bidirectional"))
      (node (ref "JP6") (pin "9") (pinfunction "9_9") (pintype "passive"))
    )
    (net (code "81") (name "PL0") (class "Default")
      (node (ref "IC3") (pin "35") (pinfunction "PL0(ICP4)_35") (pintype "bidirectional"))
      (node (ref "XIO") (pin "30") (pinfunction "30_30") (pintype "passive"))
    )
    (net (code "82") (name "PL1") (class "Default")
      (node (ref "IC3") (pin "36") (pinfunction "PL1(ICP5)_36") (pintype "bidirectional"))
      (node (ref "XIO") (pin "29") (pinfunction "29_29") (pintype "passive"))
    )
    (net (code "83") (name "PL2") (class "Default")
      (node (ref "IC3") (pin "37") (pinfunction "PL2(T5)_37") (pintype "bidirectional"))
      (node (ref "XIO") (pin "28") (pinfunction "28_28") (pintype "passive"))
    )
    (net (code "84") (name "PL3") (class "Default")
      (node (ref "IC3") (pin "38") (pinfunction "PL3(OC5A)_38") (pintype "bidirectional"))
      (node (ref "XIO") (pin "27") (pinfunction "27_27") (pintype "passive"))
    )
    (net (code "85") (name "PL4") (class "Default")
      (node (ref "IC3") (pin "39") (pinfunction "PL4(OC5B)_39") (pintype "bidirectional"))
      (node (ref "XIO") (pin "26") (pinfunction "26_26") (pintype "passive"))
    )
    (net (code "86") (name "PL5") (class "Default")
      (node (ref "IC3") (pin "40") (pinfunction "PL5(OC5C)_40") (pintype "bidirectional"))
      (node (ref "XIO") (pin "25") (pinfunction "25_25") (pintype "passive"))
    )
    (net (code "87") (name "PL6") (class "Default")
      (node (ref "IC3") (pin "41") (pinfunction "PL6_41") (pintype "bidirectional"))
      (node (ref "XIO") (pin "24") (pinfunction "24_24") (pintype "passive"))
    )
    (net (code "88") (name "PL7") (class "Default")
      (node (ref "IC3") (pin "42") (pinfunction "PL7_42") (pintype "bidirectional"))
      (node (ref "XIO") (pin "23") (pinfunction "23_23") (pintype "passive"))
    )
    (net (code "89") (name "PWRIN") (class "Default")
      (node (ref "D1") (pin "A") (pinfunction "A_A") (pintype "passive"))
      (node (ref "X1") (pin "2") (pinfunction "2_2") (pintype "power_in"))
    )
    (net (code "90") (name "RD+") (class "Default")
      (node (ref "IC4") (pin "29") (pinfunction "D+_29") (pintype "bidirectional"))
      (node (ref "RN2") (pin "4") (pinfunction "1_4") (pintype "passive"))
    )
    (net (code "91") (name "RD-") (class "Default")
      (node (ref "IC4") (pin "30") (pinfunction "D-_30") (pintype "bidirectional"))
      (node (ref "RN2") (pin "1") (pinfunction "1_1") (pintype "passive"))
    )
    (net (code "92") (name "RESET") (class "Default")
      (node (ref "C1") (pin "1") (pinfunction "1_1") (pintype "passive"))
      (node (ref "C7") (pin "2") (pinfunction "2_2") (pintype "passive"))
      (node (ref "D3") (pin "A") (pinfunction "A_A") (pintype "passive"))
      (node (ref "IC3") (pin "30") (pinfunction "RESET_30") (pintype "input"))
      (node (ref "ICSP") (pin "5") (pinfunction "5_5") (pintype "passive"))
      (node (ref "POWER") (pin "3") (pinfunction "3_3") (pintype "passive"))
      (node (ref "RESET") (pin "3") (pinfunction "3_3") (pintype "passive"))
      (node (ref "RESET") (pin "4") (pinfunction "4_4") (pintype "passive"))
      (node (ref "RESET-EN") (pin "1") (pinfunction "1_1") (pintype "passive"))
      (node (ref "RESET-EN") (pin "2") (pinfunction "2_2") (pintype "passive"))
      (node (ref "RN5") (pin "1") (pinfunction "1_1") (pintype "passive"))
    )
    (net (code "93") (name "RESET2") (class "Default")
      (node (ref "D2") (pin "A") (pinfunction "A_A") (pintype "passive"))
      (node (ref "IC4") (pin "24") (pinfunction "RESET(PC1/DW)_24") (pintype "input"))
      (node (ref "ICSP1") (pin "5") (pinfunction "5_5") (pintype "passive"))
      (node (ref "RN5") (pin "7") (pinfunction "2_7") (pintype "passive"))
    )
    (net (code "94") (name "RXD1") (class "Default")
      (node (ref "COMMUNICATION") (pin "3") (pinfunction "3_3") (pintype "passive"))
      (node (ref "IC3") (pin "45") (pinfunction "(RXD1/INT2)PD2_45") (pintype "bidirectional"))
    )
    (net (code "95") (name "RXD2") (class "Default")
      (node (ref "COMMUNICATION") (pin "5") (pinfunction "5_5") (pintype "passive"))
      (node (ref "IC3") (pin "12") (pinfunction "PH0(RXD2)_12") (pintype "bidirectional"))
    )
    (net (code "96") (name "RXD3") (class "Default")
      (node (ref "COMMUNICATION") (pin "7") (pinfunction "7_7") (pintype "passive"))
      (node (ref "IC3") (pin "63") (pinfunction "PJ0(RXD3/PCINT9)_63") (pintype "bidirectional"))
    )
    (net (code "97") (name "RXL") (class "Default")
      (node (ref "IC4") (pin "10") (pinfunction "(INT5/AIN3)PD4_10") (pintype "bidirectional"))
      (node (ref "RX") (pin "C") (pinfunction "C_C") (pintype "passive"))
    )
    (net (code "98") (name "SCK2") (class "Default")
      (node (ref "IC4") (pin "15") (pinfunction "(SCLK/PCINT1)PB1_15") (pintype "bidirectional"))
      (node (ref "ICSP1") (pin "3") (pinfunction "3_3") (pintype "passive"))
    )
    (net (code "99") (name "SCL") (class "Default")
      (node (ref "COMMUNICATION") (pin "1") (pinfunction "1_1") (pintype "passive"))
      (node (ref "IC3") (pin "43") (pinfunction "(SCL/INT0)PD0_43") (pintype "bidirectional"))
      (node (ref "JP6") (pin "1") (pinfunction "1_1") (pintype "passive"))
      (node (ref "RN1") (pin "2") (pinfunction "1_2") (pintype "passive"))
    )
    (net (code "100") (name "SDA") (class "Default")
      (node (ref "COMMUNICATION") (pin "2") (pinfunction "2_2") (pintype "passive"))
      (node (ref "IC3") (pin "44") (pinfunction "(SDA/INT1)PD1_44") (pintype "bidirectional"))
      (node (ref "JP6") (pin "2") (pinfunction "2_2") (pintype "passive"))
      (node (ref "RN1") (pin "3") (pinfunction "1_3") (pintype "passive"))
    )
    (net (code "101") (name "TXD1") (class "Default")
      (node (ref "COMMUNICATION") (pin "4") (pinfunction "4_4") (pintype "passive"))
      (node (ref "IC3") (pin "46") (pinfunction "(TXD1/INT3)PD3_46") (pintype "bidirectional"))
    )
    (net (code "102") (name "TXD2") (class "Default")
      (node (ref "COMMUNICATION") (pin "6") (pinfunction "6_6") (pintype "passive"))
      (node (ref "IC3") (pin "13") (pinfunction "PH1(TXD2)_13") (pintype "bidirectional"))
    )
    (net (code "103") (name "TXD3") (class "Default")
      (node (ref "COMMUNICATION") (pin "8") (pinfunction "8_8") (pintype "passive"))
      (node (ref "IC3") (pin "64") (pinfunction "PJ1(TXD3/PCINT10)_64") (pintype "bidirectional"))
    )
    (net (code "104") (name "TXL") (class "Default")
      (node (ref "IC4") (pin "11") (pinfunction "(XCK/AIN4/PCINT12)PD5_11") (pintype "bidirectional"))
      (node (ref "TX") (pin "C") (pinfunction "C_C") (pintype "passive"))
    )
    (net (code "105") (name "UGND") (class "Default")
      (node (ref "C10") (pin "2") (pinfunction "2_2") (pintype "passive"))
      (node (ref "GROUND") (pin "1") (pinfunction "1_1") (pintype "passive"))
      (node (ref "IC4") (pin "28") (pinfunction "UGND_28") (pintype "power_in"))
      (node (ref "L1") (pin "1") (pinfunction "1_1") (pintype "passive"))
      (node (ref "X2") (pin "4") (pinfunction "4_4") (pintype "bidirectional"))
    )
    (net (code "106") (name "USBVCC") (class "Default")
      (node (ref "C8") (pin "1") (pinfunction "1_1") (pintype "passive"))
      (node (ref "F1") (pin "1") (pinfunction "1_1") (pintype "passive"))
      (node (ref "IC4") (pin "31") (pinfunction "UVCC_31") (pintype "power_in"))
      (node (ref "T1") (pin "1") (pinfunction "D_1") (pintype "passive"))
    )
    (net (code "107") (name "USHIELD") (class "Default")
      (node (ref "L1") (pin "2") (pinfunction "2_2") (pintype "passive"))
      (node (ref "X2") (pin "P$1") (pinfunction "P$1_P$1") (pintype "bidirectional"))
      (node (ref "X2") (pin "P$2") (pinfunction "P$2_P$2") (pintype "bidirectional"))
      (node (ref "Z1") (pin "1") (pinfunction "1_1") (pintype "passive"))
      (node (ref "Z2") (pin "1") (pinfunction "1_1") (pintype "passive"))
    )
    (net (code "108") (name "VCC") (class "Default")
      (node (ref "C18") (pin "1") (pinfunction "1_1") (pintype "passive"))
      (node (ref "IC5") (pin "1") (pinfunction "VIN_1") (pintype "bidirectional"))
      (node (ref "IC5") (pin "3") (pinfunction "EN_3") (pintype "bidirectional"))
      (node (ref "JP1") (pin "1") (pinfunction "1_1") (pintype "passive"))
    )
    (net (code "109") (name "VIN") (class "Default")
      (node (ref "C2") (pin "1") (pinfunction "1_1") (pintype "passive"))
      (node (ref "D1") (pin "C") (pinfunction "C_C") (pintype "passive"))
      (node (ref "IC1") (pin "3") (pinfunction "IN_3") (pintype "input"))
      (node (ref "PC1") (pin "+") (pinfunction "+_+") (pintype "passive"))
      (node (ref "POWER") (pin "8") (pinfunction "8_8") (pintype "passive"))
      (node (ref "RN5") (pin "6") (pinfunction "2_6") (pintype "passive"))
    )
    (net (code "110") (name "VUCAP") (class "Default")
      (node (ref "C10") (pin "1") (pinfunction "1_1") (pintype "passive"))
      (node (ref "IC4") (pin "27") (pinfunction "UCAP_27") (pintype "passive"))
    )
    (net (code "111") (name "XT1") (class "Default")
      (node (ref "C14") (pin "1") (pinfunction "1_1") (pintype "passive"))
      (node (ref "IC4") (pin "1") (pinfunction "XTAL1_1") (pintype "bidirectional"))
      (node (ref "R2") (pin "1") (pinfunction "1_1") (pintype "passive"))
      (node (ref "Y2") (pin "2") (pinfunction "2_2") (pintype "passive"))
    )
    (net (code "112") (name "XT2") (class "Default")
      (node (ref "C15") (pin "1") (pinfunction "1_1") (pintype "passive"))
      (node (ref "IC4") (pin "2") (pinfunction "XTAL2(PC0)_2") (pintype "bidirectional"))
      (node (ref "R2") (pin "2") (pinfunction "2_2") (pintype "passive"))
      (node (ref "Y2") (pin "1") (pinfunction "1_1") (pintype "passive"))
    )
    (net (code "113") (name "XTAL1") (class "Default")
      (node (ref "IC3") (pin "34") (pinfunction "XTAL1_34") (pintype "input"))
      (node (ref "R1") (pin "1") (pinfunction "1_1") (pintype "passive"))
      (node (ref "Y1") (pin "3") (pinfunction "3_3") (pintype "passive"))
    )
    (net (code "114") (name "XTAL2") (class "Default")
      (node (ref "IC3") (pin "33") (pinfunction "XTAL2_33") (pintype "output"))
      (node (ref "R1") (pin "2") (pinfunction "2_2") (pintype "passive"))
      (node (ref "Y1") (pin "1") (pinfunction "1_1") (pintype "passive"))
    )
    (net (code "115") (name "XVCC") (class "Default")
      (node (ref "F1") (pin "2") (pinfunction "2_2") (pintype "passive"))
      (node (ref "X2") (pin "1") (pinfunction "1_1") (pintype "bidirectional"))
    )
    (net (code "116") (name "unconnected-(IC2E-O-Pad12)") (class "Default")
      (node (ref "IC2") (pin "12") (pinfunction "O_12") (pintype "output"))
    )
    (net (code "117") (name "unconnected-(IC2F-O-Pad15)") (class "Default")
      (node (ref "IC2") (pin "15") (pinfunction "O_15") (pintype "output"))
    )
    (net (code "118") (name "unconnected-(IC3-(CLKO{slash}ICP3{slash}INT7)PE7-Pad9)") (class "Default")
      (node (ref "IC3") (pin "9") (pinfunction "(CLKO/ICP3/INT7)PE7_9") (pintype "bidirectional"))
    )
    (net (code "119") (name "unconnected-(IC3-(ICP1)PD4-Pad47)") (class "Default")
      (node (ref "IC3") (pin "47") (pinfunction "(ICP1)PD4_47") (pintype "bidirectional"))
    )
    (net (code "120") (name "unconnected-(IC3-(T1)PD6-Pad49)") (class "Default")
      (node (ref "IC3") (pin "49") (pinfunction "(T1)PD6_49") (pintype "bidirectional"))
    )
    (net (code "121") (name "unconnected-(IC3-(T3{slash}INT6)PE6-Pad8)") (class "Default")
      (node (ref "IC3") (pin "8") (pinfunction "(T3/INT6)PE6_8") (pintype "bidirectional"))
    )
    (net (code "122") (name "unconnected-(IC3-(TOSC1)PG4-Pad29)") (class "Default")
      (node (ref "IC3") (pin "29") (pinfunction "(TOSC1)PG4_29") (pintype "bidirectional"))
    )
    (net (code "123") (name "unconnected-(IC3-(TOSC2)PG3-Pad28)") (class "Default")
      (node (ref "IC3") (pin "28") (pinfunction "(TOSC2)PG3_28") (pintype "bidirectional"))
    )
    (net (code "124") (name "unconnected-(IC3-(XCK0{slash}AIN0)PE2-Pad4)") (class "Default")
      (node (ref "IC3") (pin "4") (pinfunction "(XCK0/AIN0)PE2_4") (pintype "bidirectional"))
    )
    (net (code "125") (name "unconnected-(IC3-(XCK1)PD5-Pad48)") (class "Default")
      (node (ref "IC3") (pin "48") (pinfunction "(XCK1)PD5_48") (pintype "bidirectional"))
    )
    (net (code "126") (name "unconnected-(IC3-PH2(XCK2)-Pad14)") (class "Default")
      (node (ref "IC3") (pin "14") (pinfunction "PH2(XCK2)_14") (pintype "bidirectional"))
    )
    (net (code "127") (name "unconnected-(IC3-PH7(T4)-Pad27)") (class "Default")
      (node (ref "IC3") (pin "27") (pinfunction "PH7(T4)_27") (pintype "bidirectional"))
    )
    (net (code "128") (name "unconnected-(IC3-PJ2(XCK3{slash}PCINT11)-Pad65)") (class "Default")
      (node (ref "IC3") (pin "65") (pinfunction "PJ2(XCK3/PCINT11)_65") (pintype "bidirectional"))
    )
    (net (code "129") (name "unconnected-(IC3-PJ3(PCINT12)-Pad66)") (class "Default")
      (node (ref "IC3") (pin "66") (pinfunction "PJ3(PCINT12)_66") (pintype "bidirectional"))
    )
    (net (code "130") (name "unconnected-(IC3-PJ4(PCINT13)-Pad67)") (class "Default")
      (node (ref "IC3") (pin "67") (pinfunction "PJ4(PCINT13)_67") (pintype "bidirectional"))
    )
    (net (code "131") (name "unconnected-(IC3-PJ5(PCINT14)-Pad68)") (class "Default")
      (node (ref "IC3") (pin "68") (pinfunction "PJ5(PCINT14)_68") (pintype "bidirectional"))
    )
    (net (code "132") (name "unconnected-(IC3-PJ6(PCINT15)-Pad69)") (class "Default")
      (node (ref "IC3") (pin "69") (pinfunction "PJ6(PCINT15)_69") (pintype "bidirectional"))
    )
    (net (code "133") (name "unconnected-(IC3-PJ7-Pad79)") (class "Default")
      (node (ref "IC3") (pin "79") (pinfunction "PJ7_79") (pintype "bidirectional"))
    )
    (net (code "134") (name "unconnected-(IC3-PK0(ADC8{slash}PCINT16)-Pad89)") (class "Default")
      (node (ref "IC3") (pin "89") (pinfunction "PK0(ADC8/PCINT16)_89") (pintype "bidirectional"))
    )
    (net (code "135") (name "unconnected-(IC3-PK1(ADC9{slash}PCINT17)-Pad88)") (class "Default")
      (node (ref "IC3") (pin "88") (pinfunction "PK1(ADC9/PCINT17)_88") (pintype "bidirectional"))
    )
    (net (code "136") (name "unconnected-(IC3-PK2(ADC10{slash}PCINT18)-Pad87)") (class "Default")
      (node (ref "IC3") (pin "87") (pinfunction "PK2(ADC10/PCINT18)_87") (pintype "bidirectional"))
    )
    (net (code "137") (name "unconnected-(IC3-PK3(ADC11{slash}PCINT19)-Pad86)") (class "Default")
      (node (ref "IC3") (pin "86") (pinfunction "PK3(ADC11/PCINT19)_86") (pintype "bidirectional"))
    )
    (net (code "138") (name "unconnected-(IC3-PK4(ADC12{slash}PCINT20)-Pad85)") (class "Default")
      (node (ref "IC3") (pin "85") (pinfunction "PK4(ADC12/PCINT20)_85") (pintype "bidirectional"))
    )
    (net (code "139") (name "unconnected-(IC3-PK5(ADC13{slash}PCINT21)-Pad84)") (class "Default")
      (node (ref "IC3") (pin "84") (pinfunction "PK5(ADC13/PCINT21)_84") (pintype "bidirectional"))
    )
    (net (code "140") (name "unconnected-(IC3-PK6(ADC14{slash}PCINT22)-Pad83)") (class "Default")
      (node (ref "IC3") (pin "83") (pinfunction "PK6(ADC14/PCINT22)_83") (pintype "bidirectional"))
    )
    (net (code "141") (name "unconnected-(IC3-PK7(ADC15{slash}PCINT23)-Pad82)") (class "Default")
      (node (ref "IC3") (pin "82") (pinfunction "PK7(ADC15/PCINT23)_82") (pintype "bidirectional"))
    )
    (net (code "142") (name "unconnected-(IC4-(AIN0{slash}INT1)PD1-Pad7)") (class "Default")
      (node (ref "IC4") (pin "7") (pinfunction "(AIN0/INT1)PD1_7") (pintype "bidirectional"))
    )
    (net (code "143") (name "unconnected-(IC4-(AIN2{slash}PCINT11)PC2-Pad5)") (class "Default")
      (node (ref "IC4") (pin "5") (pinfunction "(AIN2/PCINT11)PC2_5") (pintype "bidirectional"))
    )
    (net (code "144") (name "unconnected-(IC4-(INT4{slash}ICP1{slash}CLK0)PC7-Pad22)") (class "Default")
      (node (ref "IC4") (pin "22") (pinfunction "(INT4/ICP1/CLK0)PC7_22") (pintype "bidirectional"))
    )
    (net (code "145") (name "unconnected-(IC4-(OC0B{slash}INT0)PD0-Pad6)") (class "Default")
      (node (ref "IC4") (pin "6") (pinfunction "(OC0B/INT0)PD0_6") (pintype "bidirectional"))
    )
    (net (code "146") (name "unconnected-(IC4-(OC1A{slash}PCINT8)PC6-Pad23)") (class "Default")
      (node (ref "IC4") (pin "23") (pinfunction "(OC1A/PCINT8)PC6_23") (pintype "bidirectional"))
    )
    (net (code "147") (name "unconnected-(IC4-(PCINT9{slash}OC1B)PC5-Pad25)") (class "Default")
      (node (ref "IC4") (pin "25") (pinfunction "(PCINT9/OC1B)PC5_25") (pintype "bidirectional"))
    )
    (net (code "148") (name "unconnected-(IC4-(PCINT10)PC4-Pad26)") (class "Default")
      (node (ref "IC4") (pin "26") (pinfunction "(PCINT10)PC4_26") (pintype "bidirectional"))
    )
    (net (code "149") (name "unconnected-(IC4-(RTS{slash}AIN5{slash}INT6)PD6-Pad12)") (class "Default")
      (node (ref "IC4") (pin "12") (pinfunction "(RTS/AIN5/INT6)PD6_12") (pintype "bidirectional"))
    )
    (net (code "150") (name "unconnected-(IC4-(SS{slash}PCINT0)PB0-Pad14)") (class "Default")
      (node (ref "IC4") (pin "14") (pinfunction "(SS/PCINT0)PB0_14") (pintype "bidirectional"))
    )
    (net (code "151") (name "unconnected-(IC5-BYP-Pad4)") (class "Default")
      (node (ref "IC5") (pin "4") (pinfunction "BYP_4") (pintype "bidirectional"))
    )
    (net (code "152") (name "unconnected-(IC6-NC{slash}FB-Pad4)") (class "Default")
      (node (ref "IC6") (pin "4") (pinfunction "NC/FB_4") (pintype "passive"))
    )
    (net (code "153") (name "unconnected-(POWER-Pad1)") (class "Default")
      (node (ref "POWER") (pin "1") (pinfunction "1_1") (pintype "passive"))
    )
    (net (code "154") (name "unconnected-(RN1-Pad1)") (class "Default")
      (node (ref "RN1") (pin "1") (pinfunction "1_1") (pintype "passive"))
    )
    (net (code "155") (name "unconnected-(RN1A-2-Pad8)") (class "Default")
      (node (ref "RN1") (pin "8") (pinfunction "2_8") (pintype "passive"))
    )
    (net (code "156") (name "unconnected-(RN1D-1-Pad4)") (class "Default")
      (node (ref "RN1") (pin "4") (pinfunction "1_4") (pintype "passive"))
    )
    (net (code "157") (name "unconnected-(RN1D-2-Pad5)") (class "Default")
      (node (ref "RN1") (pin "5") (pinfunction "2_5") (pintype "passive"))
    )
    (net (code "158") (name "unconnected-(RN2B-1-Pad2)") (class "Default")
      (node (ref "RN2") (pin "2") (pinfunction "1_2") (pintype "passive"))
    )
    (net (code "159") (name "unconnected-(RN2B-2-Pad7)") (class "Default")
      (node (ref "RN2") (pin "7") (pinfunction "2_7") (pintype "passive"))
    )
    (net (code "160") (name "unconnected-(RN2C-1-Pad3)") (class "Default")
      (node (ref "RN2") (pin "3") (pinfunction "1_3") (pintype "passive"))
    )
    (net (code "161") (name "unconnected-(RN2C-2-Pad6)") (class "Default")
      (node (ref "RN2") (pin "6") (pinfunction "2_6") (pintype "passive"))
    )
    (net (code "162") (name "unconnected-(RN3C-1-Pad3)") (class "Default")
      (node (ref "RN3") (pin "3") (pinfunction "1_3") (pintype "passive"))
    )
    (net (code "163") (name "unconnected-(RN3C-2-Pad6)") (class "Default")
      (node (ref "RN3") (pin "6") (pinfunction "2_6") (pintype "passive"))
    )
    (net (code "164") (name "unconnected-(X3-CARD_DETECT1-PadCD2)") (class "Default")
      (node (ref "X3") (pin "CD2") (pinfunction "CARD_DETECT1_CD2") (pintype "passive"))
    )
    (net (code "165") (name "unconnected-(X3-DAT1-Pad8)") (class "Default")
      (node (ref "X3") (pin "8") (pinfunction "DAT1_8") (pintype "bidirectional"))
    )
    (net (code "166") (name "unconnected-(X3-DAT2-Pad1)") (class "Default")
      (node (ref "X3") (pin "1") (pinfunction "DAT2_1") (pintype "bidirectional"))
    )
  )
)
